# LineSensorModuleSchematic.net
KiCad netlist of a schematic drawn in Altium Designer
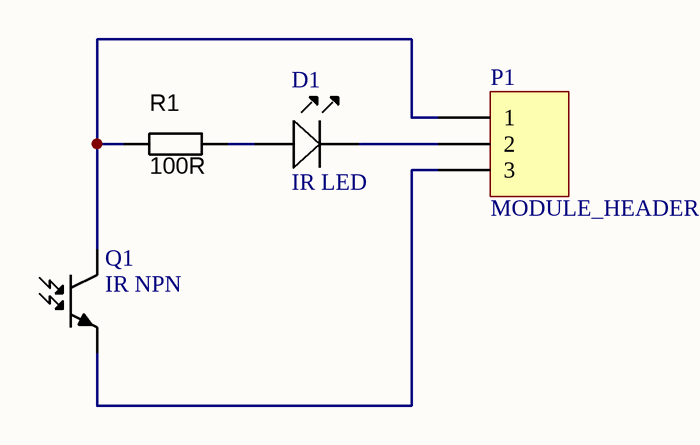
[diagram p0: LineSensorModuleSchematic.SchDoc]

(export (version "E")
  (design (tool "Eeschema 10.0.6"))
  (components
    (comp (ref "D1")
      (value "IR LED")
      (footprint "STDLED")
      (libsource (lib "LineSensorComponents") (part "IR_LED"))
    )
    (comp (ref "P1")
      (value "MODULE_HEADER")
      (footprint "HDR1X3")
      (description "Header, 3-Pin")
      (fields (field (name "PUBLISHER") "Altium Limited"))
      (libsource (lib "Miscellaneous Connectors") (part "Header 3"))
    )
    (comp (ref "Q1")
      (value "IR NPN")
      (footprint "IRNPN")
      (libsource (lib "LineSensorComponents") (part "IR_NPN"))
    )
    (comp (ref "R1")
      (value "100R")
      (footprint "RESC3216N_ZERO")
      (description "Resistor SMD chip 0.0 Ohm 0.25W 1206")
      (fields (field (name "TOLERANCE") "±5%") (field (name "Comment") "Thick Film"))
      (libsource (lib "PBL - Resistors") (part "RES_0R_1206"))
    )
  )
  (nets
    (net (code "1") (name "Net-(D1-PadA)") (class "Default")
      (node (ref "D1") (pin "A") (pinfunction "A_A") (pintype "passive"))
      (node (ref "R1") (pin "2") (pinfunction "2_2") (pintype "passive"))
    )
    (net (code "2") (name "Net-(D1-PadK)") (class "Default")
      (node (ref "D1") (pin "K") (pinfunction "K_K") (pintype "passive"))
      (node (ref "P1") (pin "2") (pinfunction "2_2") (pintype "passive"))
    )
    (net (code "3") (name "Net-(Q1-C)") (class "Default")
      (node (ref "P1") (pin "1") (pinfunction "1_1") (pintype "passive"))
      (node (ref "Q1") (pin "3") (pinfunction "C_3") (pintype "passive"))
      (node (ref "R1") (pin "1") (pinfunction "1_1") (pintype "passive"))
    )
    (net (code "4") (name "Net-(Q1-E)") (class "Default")
      (node (ref "P1") (pin "3") (pinfunction "3_3") (pintype "passive"))
      (node (ref "Q1") (pin "1") (pinfunction "E_1") (pintype "passive"))
    )
  )
)
